# 3_STM32F103_Debugger.net
KiCad netlist of a schematic drawn in Altium Designer
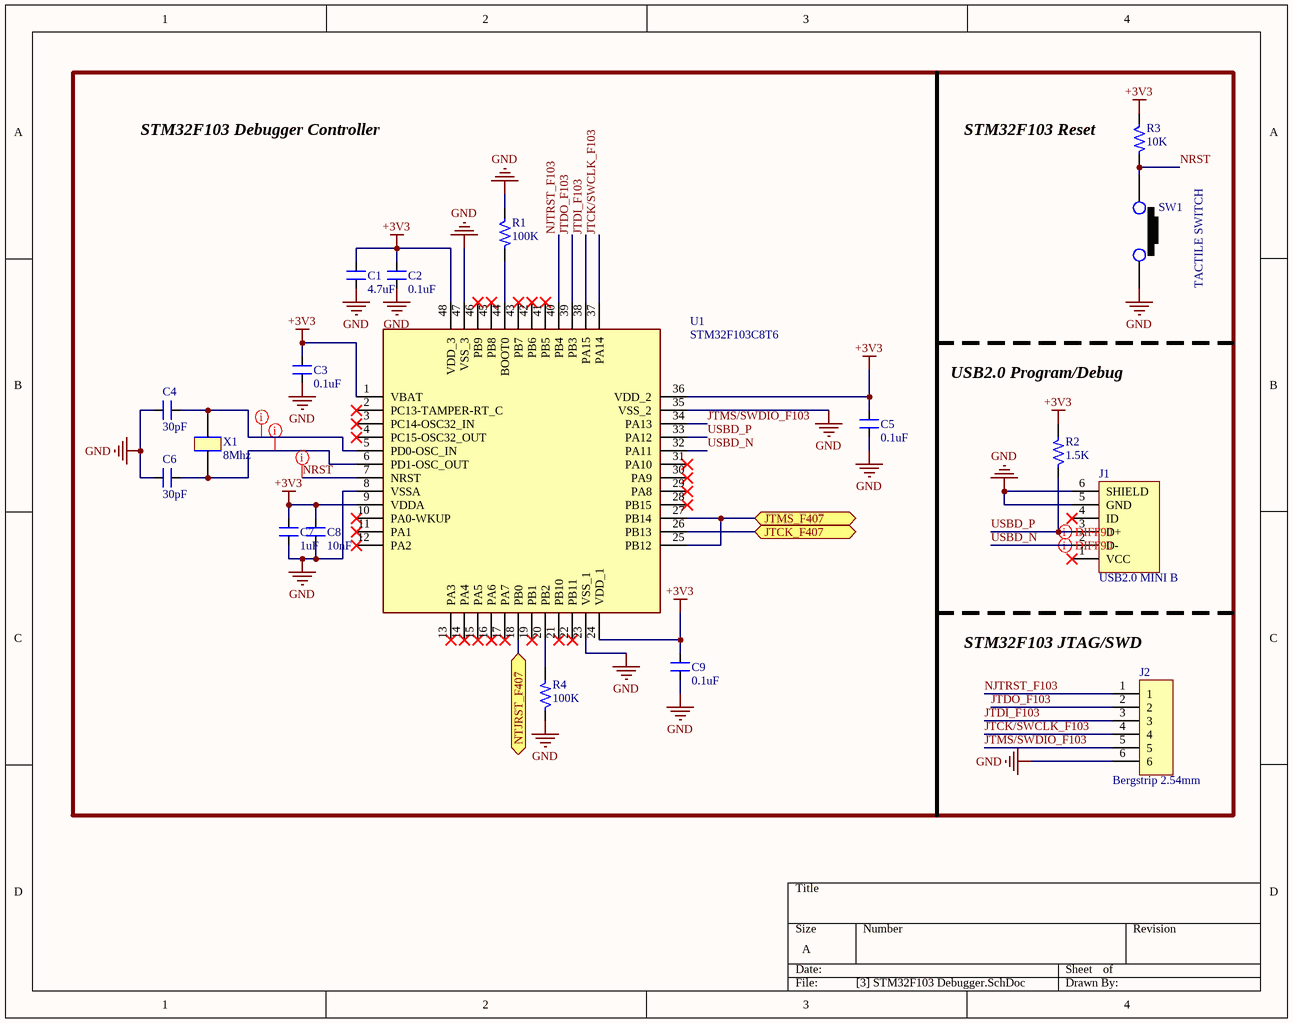
[diagram p0: [3] STM32F103 Debugger.SchDoc]

(export (version "E")
  (design (tool "Eeschema 10.0.6"))
  (components
    (comp (ref "C1")
      (value "4.7uF")
      (footprint "CAP_0805")
      (description "4.7µF ±10% 50V Ceramic Capacitor X5R 0805 (2012 Metric)")
      (fields
        (field (name "MANUFACTURER") "Yageo")
        (field (name "MANUFACTURER PART NUMBER") "GRM21BR61H475KE51L")
      )
      (libsource (lib "ESTEEMPCBLIB") (part "CAP_4.7uF-50V-10%-0805"))
    )
    (comp (ref "C2")
      (value "0.1uF")
      (footprint "CAP_0805")
      (description "0.1µF ±10% 50V Ceramic Capacitor X7R 0805 (2012 Metric)")
      (fields
        (field (name "MANUFACTURER") "Samsung")
        (field (name "MANUFACTURER PART NUMBER") "CL21B104KBCNNNC")
      )
      (libsource (lib "ESTEEMPCBLIB") (part "CAP_0.1uF-50V-10%-0805"))
    )
    (comp (ref "C3")
      (value "0.1uF")
      (footprint "CAP_0805")
      (description "0.1µF ±10% 50V Ceramic Capacitor X7R 0805 (2012 Metric)")
      (fields
        (field (name "MANUFACTURER") "Samsung")
        (field (name "MANUFACTURER PART NUMBER") "CL21B104KBCNNNC")
      )
      (libsource (lib "ESTEEMPCBLIB") (part "CAP_0.1uF-50V-10%-0805"))
    )
    (comp (ref "C4")
      (value "30pF")
      (footprint "CAP_0805")
      (description "±10% 50V Ceramic Capacitor C0G, NP0 0805 (2012 Metric)")
      (fields
        (field (name "MANUFACTURER PART NUMBER") "C0805C300K5GAC7800")
        (field (name "MANUFACTURER") "KEMET")
      )
      (libsource (lib "ESTEEMPCBLIB") (part "CAP_30pF-50V-10%-0805"))
    )
    (comp (ref "C5")
      (value "0.1uF")
      (footprint "CAP_0805")
      (description "0.1µF ±10% 50V Ceramic Capacitor X7R 0805 (2012 Metric)")
      (fields
        (field (name "MANUFACTURER") "Samsung")
        (field (name "MANUFACTURER PART NUMBER") "CL21B104KBCNNNC")
      )
      (libsource (lib "ESTEEMPCBLIB") (part "CAP_0.1uF-50V-10%-0805"))
    )
    (comp (ref "C6")
      (value "30pF")
      (footprint "CAP_0805")
      (description "±10% 50V Ceramic Capacitor C0G, NP0 0805 (2012 Metric)")
      (fields
        (field (name "MANUFACTURER PART NUMBER") "C0805C300K5GAC7800")
        (field (name "MANUFACTURER") "KEMET")
      )
      (libsource (lib "ESTEEMPCBLIB") (part "CAP_30pF-50V-10%-0805"))
    )
    (comp (ref "C7")
      (value "1uF")
      (footprint "CAP_0805")
      (description "1µF ±5% 50V Ceramic Capacitor X7R 0805 (2012 Metric)")
      (fields
        (field (name "MANUFACTURER") "Samsung")
        (field (name "MANUFACTURER PART NUMBER") "CC0805JKX7R9BB105")
      )
      (libsource (lib "ESTEEMPCBLIB") (part "CAP_1uF-50V-5%-0805"))
    )
    (comp (ref "C8")
      (value "10nF")
      (footprint "CAP_0805")
      (description "10000pF ±10% 50V Ceramic Capacitor X7R 0805 (2012 Metric)")
      (fields
        (field (name "MANUFACTURER") "Samsung")
        (field (name "MANUFACTURER PART NUMBER") "C0805C103K5RECAUTO")
      )
      (libsource (lib "ESTEEMPCBLIB") (part "CAP_10nF-50V-10%-0805"))
    )
    (comp (ref "C9")
      (value "0.1uF")
      (footprint "CAP_0805")
      (description "0.1µF ±10% 50V Ceramic Capacitor X7R 0805 (2012 Metric)")
      (fields
        (field (name "MANUFACTURER") "Samsung")
        (field (name "MANUFACTURER PART NUMBER") "CL21B104KBCNNNC")
      )
      (libsource (lib "ESTEEMPCBLIB") (part "CAP_0.1uF-50V-10%-0805"))
    )
    (comp (ref "J1")
      (value "USB2.0 MINI B")
      (footprint "CON_690-005-299-043")
      (description "USB - mini B USB 2.0 Receptacle Connector 5 Position Surface Mount, Right Angle")
      (fields
        (field (name "MANUFACTURER") "EDAC")
        (field (name "MANUFACTURER PART NUMBER") "690-005-299-043")
      )
      (libsource (lib "ESTEEMPCBLIB") (part "CON_USB2.0-MINIB-SMD"))
    )
    (comp (ref "J2")
      (value "Bergstrip 2.54mm")
      (footprint "CON6_100_59D78_TH_ST")
      (description "6 Pins, 1 Row 2.54mm Pitch, Straight bergstrip, Female")
      (fields (field (name "MANUFACTURER") "Molex") (field (name "MANUFACTURER PART NUMBER") "22-10-2061"))
      (libsource (lib "ESTEEMPCBLIB") (part "CON-BS-SKT_6X1-100-ST-TH"))
    )
    (comp (ref "R1")
      (value "100K")
      (footprint "RES_0603")
      (description "100 kOhms ±1% 0.1W, 1/10W Chip Resistor 0603 (1608 Metric) Automotive AEC-Q200 Thick Film")
      (fields
        (field (name "MANUFACTURER") "Stackpole Electronics")
        (field (name "MANUFACTURER PART NUMBER") "RMCF0603FT100K")
      )
      (libsource (lib "ESTEEMPCBLIB") (part "RES_100K-0.1W-1%-0603"))
    )
    (comp (ref "R2")
      (value "1.5K")
      (footprint "RES_0805")
      (description "1.5 kOhms ±1% 0.125W, 1/8W Chip Resistor 0805 (2012 Metric) Thick Film")
      (fields
        (field (name "MANUFACTURER") "TE Connectivity Passive Product")
        (field (name "MANUFACTURER PART NUMBER") "CRG0805F1K5")
      )
      (libsource (lib "ESTEEMPCBLIB") (part "RES_1.5K-0.125W-1%-0805"))
    )
    (comp (ref "R3")
      (value "10K")
      (footprint "RES_0603")
      (description "10 kOhms ±1% 0.1W, 1/10W Chip Resistor 0603 (1608 Metric) Automotive AEC-Q200 Thick Film")
      (fields (field (name "MANUFACTURER") "Walsin") (field (name "MANUFACTURER PART NUMBER") "WR06X1002FTL"))
      (libsource (lib "ESTEEMPCBLIB") (part "RES_10K-0.1W-1%-0603"))
    )
    (comp (ref "R4")
      (value "100K")
      (footprint "RES_0603")
      (description "100 kOhms ±1% 0.1W, 1/10W Chip Resistor 0603 (1608 Metric) Automotive AEC-Q200 Thick Film")
      (fields
        (field (name "MANUFACTURER") "Stackpole Electronics")
        (field (name "MANUFACTURER PART NUMBER") "RMCF0603FT100K")
      )
      (libsource (lib "ESTEEMPCBLIB") (part "RES_100K-0.1W-1%-0603"))
    )
    (comp (ref "SW1")
      (value "TACTILE SWITCH")
      (footprint "SW_342_SMD")
      (description "Tactile Switch SPST-NO Top Actuated Surface Mount")
      (fields
        (field (name "MANUFACTURER") "ITT C&K")
        (field (name "MANUFACTURER PART NUMBER") "RS-282G05A3-SMRT")
      )
      (libsource (lib "ESTEEMPCBLIB") (part "SW1_RS-282G05A3-SMRT-SMD"))
    )
    (comp (ref "U1")
      (value "STM32F103C8T6")
      (footprint "LQFP-48_19.6_393_58X11_SMD")
      (description "ARM® Cortex®-M3 STM32F1 Microcontroller IC 32-Bit 72MHz 64KB (64K x 8) FLASH 48-LQFP (7x7)")
      (fields (field (name "MANUFACTURER") "STMicroelectronics"))
      (libsource (lib "ESTEEMPCBLIB") (part "IC_STM32F103C8T6"))
    )
    (comp (ref "X1")
      (value "8Mhz")
      (footprint "XTAL_314_240X47_SMD")
      (description "8MHz ±30ppm Crystal 32pF 60 Ohms HC-49/US")
      (fields
        (field (name "MANUFACTURER") "Fox Electronics")
        (field (name "MANUFACTURER PART NUMBER") "ECS-80-32-5PX-TR")
      )
      (libsource (lib "ESTEEMPCBLIB") (part "XTAL_8MHZ-ECS-80-32-5PX-SMD"))
    )
  )
  (nets
    (net (code "1") (name "+3V3") (class "Default")
      (node (ref "C1") (pin "2") (pinfunction "2_2") (pintype "passive"))
      (node (ref "C2") (pin "2") (pinfunction "2_2") (pintype "passive"))
      (node (ref "C3") (pin "2") (pinfunction "2_2") (pintype "passive"))
      (node (ref "C5") (pin "2") (pinfunction "2_2") (pintype "passive"))
      (node (ref "C7") (pin "2") (pinfunction "2_2") (pintype "passive"))
      (node (ref "C8") (pin "2") (pinfunction "2_2") (pintype "passive"))
      (node (ref "C9") (pin "2") (pinfunction "2_2") (pintype "passive"))
      (node (ref "R2") (pin "2") (pinfunction "2_2") (pintype "passive"))
      (node (ref "R3") (pin "1") (pinfunction "1_1") (pintype "passive"))
      (node (ref "U1") (pin "1") (pinfunction "VBAT_1") (pintype "passive"))
      (node (ref "U1") (pin "24") (pinfunction "VDD_1_24") (pintype "passive"))
      (node (ref "U1") (pin "36") (pinfunction "VDD_2_36") (pintype "passive"))
      (node (ref "U1") (pin "48") (pinfunction "VDD_3_48") (pintype "passive"))
      (node (ref "U1") (pin "9") (pinfunction "VDDA_9") (pintype "passive"))
    )
    (net (code "2") (name "/JTCK_F407") (class "Default")
      (node (ref "U1") (pin "26") (pinfunction "PB13_26") (pintype "passive"))
    )
    (net (code "3") (name "/JTCK{slash}SWCLK_F103") (class "Default")
      (node (ref "J2") (pin "4") (pinfunction "4_4") (pintype "passive"))
      (node (ref "U1") (pin "37") (pinfunction "PA14_37") (pintype "passive"))
    )
    (net (code "4") (name "/JTDI_F103") (class "Default")
      (node (ref "J2") (pin "3") (pinfunction "3_3") (pintype "passive"))
      (node (ref "U1") (pin "38") (pinfunction "PA15_38") (pintype "passive"))
    )
    (net (code "5") (name "/JTDO_F103") (class "Default")
      (node (ref "J2") (pin "2") (pinfunction "2_2") (pintype "passive"))
      (node (ref "U1") (pin "39") (pinfunction "PB3_39") (pintype "passive"))
    )
    (net (code "6") (name "/JTMS_F407") (class "Default")
      (node (ref "U1") (pin "25") (pinfunction "PB12_25") (pintype "passive"))
      (node (ref "U1") (pin "27") (pinfunction "PB14_27") (pintype "passive"))
    )
    (net (code "7") (name "/JTMS{slash}SWDIO_F103") (class "Default")
      (node (ref "J2") (pin "5") (pinfunction "5_5") (pintype "passive"))
      (node (ref "U1") (pin "34") (pinfunction "PA13_34") (pintype "passive"))
    )
    (net (code "8") (name "/NJTRST_F103") (class "Default")
      (node (ref "J2") (pin "1") (pinfunction "1_1") (pintype "passive"))
      (node (ref "U1") (pin "40") (pinfunction "PB4_40") (pintype "passive"))
    )
    (net (code "9") (name "/NRST") (class "Default")
      (node (ref "R3") (pin "2") (pinfunction "2_2") (pintype "passive"))
      (node (ref "SW1") (pin "1") (pinfunction "1_1") (pintype "passive"))
      (node (ref "U1") (pin "7") (pinfunction "NRST_7") (pintype "passive"))
    )
    (net (code "10") (name "/NTJRST_F407") (class "Default")
      (node (ref "U1") (pin "18") (pinfunction "PB0_18") (pintype "passive"))
    )
    (net (code "11") (name "/USBD_N") (class "Default")
      (node (ref "J1") (pin "2") (pinfunction "D-_2") (pintype "passive"))
      (node (ref "U1") (pin "32") (pinfunction "PA11_32") (pintype "passive"))
    )
    (net (code "12") (name "/USBD_P") (class "Default")
      (node (ref "J1") (pin "3") (pinfunction "D+_3") (pintype "passive"))
      (node (ref "R2") (pin "1") (pinfunction "1_1") (pintype "passive"))
      (node (ref "U1") (pin "33") (pinfunction "PA12_33") (pintype "passive"))
    )
    (net (code "13") (name "GND") (class "Default")
      (node (ref "C1") (pin "1") (pinfunction "1_1") (pintype "passive"))
      (node (ref "C2") (pin "1") (pinfunction "1_1") (pintype "passive"))
      (node (ref "C3") (pin "1") (pinfunction "1_1") (pintype "passive"))
      (node (ref "C4") (pin "1") (pinfunction "1_1") (pintype "passive"))
      (node (ref "C5") (pin "1") (pinfunction "1_1") (pintype "passive"))
      (node (ref "C6") (pin "1") (pinfunction "1_1") (pintype "passive"))
      (node (ref "C7") (pin "1") (pinfunction "1_1") (pintype "passive"))
      (node (ref "C8") (pin "1") (pinfunction "1_1") (pintype "passive"))
      (node (ref "C9") (pin "1") (pinfunction "1_1") (pintype "passive"))
      (node (ref "J1") (pin "5") (pinfunction "GND_5") (pintype "passive"))
      (node (ref "J1") (pin "6") (pinfunction "SHIELD_6") (pintype "passive"))
      (node (ref "J2") (pin "6") (pinfunction "6_6") (pintype "passive"))
      (node (ref "R1") (pin "1") (pinfunction "1_1") (pintype "passive"))
      (node (ref "R4") (pin "1") (pinfunction "1_1") (pintype "passive"))
      (node (ref "SW1") (pin "2") (pinfunction "2_2") (pintype "passive"))
      (node (ref "U1") (pin "23") (pinfunction "VSS_1_23") (pintype "passive"))
      (node (ref "U1") (pin "35") (pinfunction "VSS_2_35") (pintype "passive"))
      (node (ref "U1") (pin "47") (pinfunction "VSS_3_47") (pintype "passive"))
      (node (ref "U1") (pin "8") (pinfunction "VSSA_8") (pintype "passive"))
    )
    (net (code "14") (name "Net-(U1-BOOT0)") (class "Default")
      (node (ref "R1") (pin "2") (pinfunction "2_2") (pintype "passive"))
      (node (ref "U1") (pin "44") (pinfunction "BOOT0_44") (pintype "passive"))
    )
    (net (code "15") (name "Net-(U1-PB2)") (class "Default")
      (node (ref "R4") (pin "2") (pinfunction "2_2") (pintype "passive"))
      (node (ref "U1") (pin "20") (pinfunction "PB2_20") (pintype "passive"))
    )
    (net (code "16") (name "Net-(U1-PD0-OSC_IN)") (class "Default")
      (node (ref "C4") (pin "2") (pinfunction "2_2") (pintype "passive"))
      (node (ref "U1") (pin "5") (pinfunction "PD0-OSC_IN_5") (pintype "passive"))
      (node (ref "X1") (pin "2") (pinfunction "2_2") (pintype "passive"))
    )
    (net (code "17") (name "Net-(U1-PD1-OSC_OUT)") (class "Default")
      (node (ref "C6") (pin "2") (pinfunction "2_2") (pintype "passive"))
      (node (ref "U1") (pin "6") (pinfunction "PD1-OSC_OUT_6") (pintype "passive"))
      (node (ref "X1") (pin "1") (pinfunction "1_1") (pintype "passive"))
    )
    (net (code "18") (name "unconnected-(J1-ID-Pad4)") (class "Default")
      (node (ref "J1") (pin "4") (pinfunction "ID_4") (pintype "passive+no_connect"))
    )
    (net (code "19") (name "unconnected-(J1-VCC-Pad1)") (class "Default")
      (node (ref "J1") (pin "1") (pinfunction "VCC_1") (pintype "passive+no_connect"))
    )
    (net (code "20") (name "unconnected-(U1-PA0-WKUP-Pad10)") (class "Default")
      (node (ref "U1") (pin "10") (pinfunction "PA0-WKUP_10") (pintype "passive+no_connect"))
    )
    (net (code "21") (name "unconnected-(U1-PA1-Pad11)") (class "Default")
      (node (ref "U1") (pin "11") (pinfunction "PA1_11") (pintype "passive+no_connect"))
    )
    (net (code "22") (name "unconnected-(U1-PA2-Pad12)") (class "Default")
      (node (ref "U1") (pin "12") (pinfunction "PA2_12") (pintype "passive+no_connect"))
    )
    (net (code "23") (name "unconnected-(U1-PA3-Pad13)") (class "Default")
      (node (ref "U1") (pin "13") (pinfunction "PA3_13") (pintype "passive+no_connect"))
    )
    (net (code "24") (name "unconnected-(U1-PA4-Pad14)") (class "Default")
      (node (ref "U1") (pin "14") (pinfunction "PA4_14") (pintype "passive+no_connect"))
    )
    (net (code "25") (name "unconnected-(U1-PA5-Pad15)") (class "Default")
      (node (ref "U1") (pin "15") (pinfunction "PA5_15") (pintype "passive+no_connect"))
    )
    (net (code "26") (name "unconnected-(U1-PA6-Pad16)") (class "Default")
      (node (ref "U1") (pin "16") (pinfunction "PA6_16") (pintype "passive+no_connect"))
    )
    (net (code "27") (name "unconnected-(U1-PA7-Pad17)") (class "Default")
      (node (ref "U1") (pin "17") (pinfunction "PA7_17") (pintype "passive+no_connect"))
    )
    (net (code "28") (name "unconnected-(U1-PA8-Pad29)") (class "Default")
      (node (ref "U1") (pin "29") (pinfunction "PA8_29") (pintype "passive+no_connect"))
    )
    (net (code "29") (name "unconnected-(U1-PA9-Pad30)") (class "Default")
      (node (ref "U1") (pin "30") (pinfunction "PA9_30") (pintype "passive+no_connect"))
    )
    (net (code "30") (name "unconnected-(U1-PA10-Pad31)") (class "Default")
      (node (ref "U1") (pin "31") (pinfunction "PA10_31") (pintype "passive+no_connect"))
    )
    (net (code "31") (name "unconnected-(U1-PB1-Pad19)") (class "Default")
      (node (ref "U1") (pin "19") (pinfunction "PB1_19") (pintype "passive+no_connect"))
    )
    (net (code "32") (name "unconnected-(U1-PB5-Pad41)") (class "Default")
      (node (ref "U1") (pin "41") (pinfunction "PB5_41") (pintype "passive+no_connect"))
    )
    (net (code "33") (name "unconnected-(U1-PB6-Pad42)") (class "Default")
      (node (ref "U1") (pin "42") (pinfunction "PB6_42") (pintype "passive+no_connect"))
    )
    (net (code "34") (name "unconnected-(U1-PB7-Pad43)") (class "Default")
      (node (ref "U1") (pin "43") (pinfunction "PB7_43") (pintype "passive+no_connect"))
    )
    (net (code "35") (name "unconnected-(U1-PB8-Pad45)") (class "Default")
      (node (ref "U1") (pin "45") (pinfunction "PB8_45") (pintype "passive+no_connect"))
    )
    (net (code "36") (name "unconnected-(U1-PB9-Pad46)") (class "Default")
      (node (ref "U1") (pin "46") (pinfunction "PB9_46") (pintype "passive+no_connect"))
    )
    (net (code "37") (name "unconnected-(U1-PB10-Pad21)") (class "Default")
      (node (ref "U1") (pin "21") (pinfunction "PB10_21") (pintype "passive+no_connect"))
    )
    (net (code "38") (name "unconnected-(U1-PB11-Pad22)") (class "Default")
      (node (ref "U1") (pin "22") (pinfunction "PB11_22") (pintype "passive+no_connect"))
    )
    (net (code "39") (name "unconnected-(U1-PB15-Pad28)") (class "Default")
      (node (ref "U1") (pin "28") (pinfunction "PB15_28") (pintype "passive+no_connect"))
    )
    (net (code "40") (name "unconnected-(U1-PC13-TAMPER-RT_C-Pad2)") (class "Default")
      (node (ref "U1") (pin "2") (pinfunction "PC13-TAMPER-RT_C_2") (pintype "passive+no_connect"))
    )
    (net (code "41") (name "unconnected-(U1-PC14-OSC32_IN-Pad3)") (class "Default")
      (node (ref "U1") (pin "3") (pinfunction "PC14-OSC32_IN_3") (pintype "passive+no_connect"))
    )
    (net (code "42") (name "unconnected-(U1-PC15-OSC32_OUT-Pad4)") (class "Default")
      (node (ref "U1") (pin "4") (pinfunction "PC15-OSC32_OUT_4") (pintype "passive+no_connect"))
    )
  )
)
